# LED3.net
KiCad netlist of a schematic drawn in Altium Designer
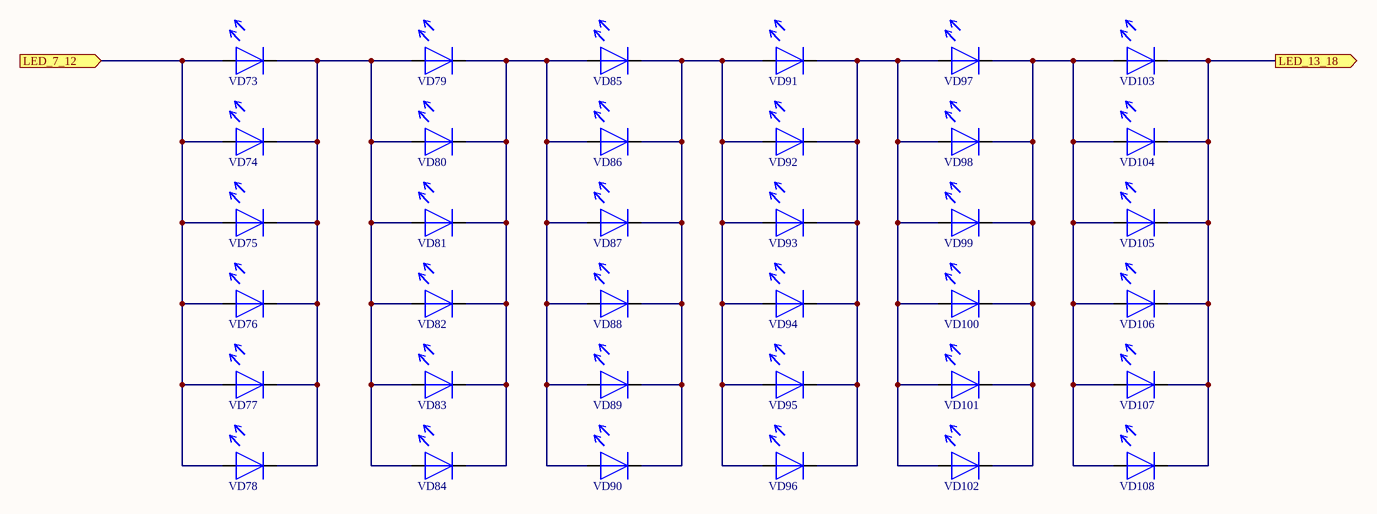
[diagram p0: LED3.SchDoc]

(export (version "E")
  (design (tool "Eeschema 10.0.6"))
  (components
    (comp (ref "VD73")
      (value "SPMWHT541MD5WAT0SB")
      (footprint "LED_Samsung")
      (libsource (lib "gprs_modem_2") (part "LED SPMWHT541MD5WAT0SB"))
    )
    (comp (ref "VD74")
      (value "SPMWHT541MD5WAT0SB")
      (footprint "LED_Samsung")
      (libsource (lib "gprs_modem_2") (part "LED SPMWHT541MD5WAT0SB"))
    )
    (comp (ref "VD75")
      (value "SPMWHT541MD5WAT0SB")
      (footprint "LED_Samsung")
      (libsource (lib "gprs_modem_2") (part "LED SPMWHT541MD5WAT0SB"))
    )
    (comp (ref "VD76")
      (value "SPMWHT541MD5WAT0SB")
      (footprint "LED_Samsung")
      (libsource (lib "gprs_modem_2") (part "LED SPMWHT541MD5WAT0SB"))
    )
    (comp (ref "VD77")
      (value "SPMWHT541MD5WAT0SB")
      (footprint "LED_Samsung")
      (libsource (lib "gprs_modem_2") (part "LED SPMWHT541MD5WAT0SB"))
    )
    (comp (ref "VD78")
      (value "SPMWHT541MD5WAT0SB")
      (footprint "LED_Samsung")
      (libsource (lib "gprs_modem_2") (part "LED SPMWHT541MD5WAT0SB"))
    )
    (comp (ref "VD79")
      (value "SPMWHT541MD5WAT0SB")
      (footprint "LED_Samsung")
      (libsource (lib "gprs_modem_2") (part "LED SPMWHT541MD5WAT0SB"))
    )
    (comp (ref "VD80")
      (value "SPMWHT541MD5WAT0SB")
      (footprint "LED_Samsung")
      (libsource (lib "gprs_modem_2") (part "LED SPMWHT541MD5WAT0SB"))
    )
    (comp (ref "VD81")
      (value "SPMWHT541MD5WAT0SB")
      (footprint "LED_Samsung")
      (libsource (lib "gprs_modem_2") (part "LED SPMWHT541MD5WAT0SB"))
    )
    (comp (ref "VD82")
      (value "SPMWHT541MD5WAT0SB")
      (footprint "LED_Samsung")
      (libsource (lib "gprs_modem_2") (part "LED SPMWHT541MD5WAT0SB"))
    )
    (comp (ref "VD83")
      (value "SPMWHT541MD5WAT0SB")
      (footprint "LED_Samsung")
      (libsource (lib "gprs_modem_2") (part "LED SPMWHT541MD5WAT0SB"))
    )
    (comp (ref "VD84")
      (value "SPMWHT541MD5WAT0SB")
      (footprint "LED_Samsung")
      (libsource (lib "gprs_modem_2") (part "LED SPMWHT541MD5WAT0SB"))
    )
    (comp (ref "VD85")
      (value "SPMWHT541MD5WAT0SB")
      (footprint "LED_Samsung")
      (libsource (lib "gprs_modem_2") (part "LED SPMWHT541MD5WAT0SB"))
    )
    (comp (ref "VD86")
      (value "SPMWHT541MD5WAT0SB")
      (footprint "LED_Samsung")
      (libsource (lib "gprs_modem_2") (part "LED SPMWHT541MD5WAT0SB"))
    )
    (comp (ref "VD87")
      (value "SPMWHT541MD5WAT0SB")
      (footprint "LED_Samsung")
      (libsource (lib "gprs_modem_2") (part "LED SPMWHT541MD5WAT0SB"))
    )
    (comp (ref "VD88")
      (value "SPMWHT541MD5WAT0SB")
      (footprint "LED_Samsung")
      (libsource (lib "gprs_modem_2") (part "LED SPMWHT541MD5WAT0SB"))
    )
    (comp (ref "VD89")
      (value "SPMWHT541MD5WAT0SB")
      (footprint "LED_Samsung")
      (libsource (lib "gprs_modem_2") (part "LED SPMWHT541MD5WAT0SB"))
    )
    (comp (ref "VD90")
      (value "SPMWHT541MD5WAT0SB")
      (footprint "LED_Samsung")
      (libsource (lib "gprs_modem_2") (part "LED SPMWHT541MD5WAT0SB"))
    )
    (comp (ref "VD91")
      (value "SPMWHT541MD5WAT0SB")
      (footprint "LED_Samsung")
      (libsource (lib "gprs_modem_2") (part "LED SPMWHT541MD5WAT0SB"))
    )
    (comp (ref "VD92")
      (value "SPMWHT541MD5WAT0SB")
      (footprint "LED_Samsung")
      (libsource (lib "gprs_modem_2") (part "LED SPMWHT541MD5WAT0SB"))
    )
    (comp (ref "VD93")
      (value "SPMWHT541MD5WAT0SB")
      (footprint "LED_Samsung")
      (libsource (lib "gprs_modem_2") (part "LED SPMWHT541MD5WAT0SB"))
    )
    (comp (ref "VD94")
      (value "SPMWHT541MD5WAT0SB")
      (footprint "LED_Samsung")
      (libsource (lib "gprs_modem_2") (part "LED SPMWHT541MD5WAT0SB"))
    )
    (comp (ref "VD95")
      (value "SPMWHT541MD5WAT0SB")
      (footprint "LED_Samsung")
      (libsource (lib "gprs_modem_2") (part "LED SPMWHT541MD5WAT0SB"))
    )
    (comp (ref "VD96")
      (value "SPMWHT541MD5WAT0SB")
      (footprint "LED_Samsung")
      (libsource (lib "gprs_modem_2") (part "LED SPMWHT541MD5WAT0SB"))
    )
    (comp (ref "VD97")
      (value "SPMWHT541MD5WAT0SB")
      (footprint "LED_Samsung")
      (libsource (lib "gprs_modem_2") (part "LED SPMWHT541MD5WAT0SB"))
    )
    (comp (ref "VD98")
      (value "SPMWHT541MD5WAT0SB")
      (footprint "LED_Samsung")
      (libsource (lib "gprs_modem_2") (part "LED SPMWHT541MD5WAT0SB"))
    )
    (comp (ref "VD99")
      (value "SPMWHT541MD5WAT0SB")
      (footprint "LED_Samsung")
      (libsource (lib "gprs_modem_2") (part "LED SPMWHT541MD5WAT0SB"))
    )
    (comp (ref "VD100")
      (value "SPMWHT541MD5WAT0SB")
      (footprint "LED_Samsung")
      (libsource (lib "gprs_modem_2") (part "LED SPMWHT541MD5WAT0SB"))
    )
    (comp (ref "VD101")
      (value "SPMWHT541MD5WAT0SB")
      (footprint "LED_Samsung")
      (libsource (lib "gprs_modem_2") (part "LED SPMWHT541MD5WAT0SB"))
    )
    (comp (ref "VD102")
      (value "SPMWHT541MD5WAT0SB")
      (footprint "LED_Samsung")
      (libsource (lib "gprs_modem_2") (part "LED SPMWHT541MD5WAT0SB"))
    )
    (comp (ref "VD103")
      (value "SPMWHT541MD5WAT0SB")
      (footprint "LED_Samsung")
      (libsource (lib "gprs_modem_2") (part "LED SPMWHT541MD5WAT0SB"))
    )
    (comp (ref "VD104")
      (value "SPMWHT541MD5WAT0SB")
      (footprint "LED_Samsung")
      (libsource (lib "gprs_modem_2") (part "LED SPMWHT541MD5WAT0SB"))
    )
    (comp (ref "VD105")
      (value "SPMWHT541MD5WAT0SB")
      (footprint "LED_Samsung")
      (libsource (lib "gprs_modem_2") (part "LED SPMWHT541MD5WAT0SB"))
    )
    (comp (ref "VD106")
      (value "SPMWHT541MD5WAT0SB")
      (footprint "LED_Samsung")
      (libsource (lib "gprs_modem_2") (part "LED SPMWHT541MD5WAT0SB"))
    )
    (comp (ref "VD107")
      (value "SPMWHT541MD5WAT0SB")
      (footprint "LED_Samsung")
      (libsource (lib "gprs_modem_2") (part "LED SPMWHT541MD5WAT0SB"))
    )
    (comp (ref "VD108")
      (value "SPMWHT541MD5WAT0SB")
      (footprint "LED_Samsung")
      (libsource (lib "gprs_modem_2") (part "LED SPMWHT541MD5WAT0SB"))
    )
  )
  (nets
    (net (code "1") (name "/LED_7_12") (class "Default")
      (node (ref "VD73") (pin "1") (pintype "passive"))
      (node (ref "VD74") (pin "1") (pintype "passive"))
      (node (ref "VD75") (pin "1") (pintype "passive"))
      (node (ref "VD76") (pin "1") (pintype "passive"))
      (node (ref "VD77") (pin "1") (pintype "passive"))
      (node (ref "VD78") (pin "1") (pintype "passive"))
    )
    (net (code "2") (name "/LED_13_18") (class "Default")
      (node (ref "VD103") (pin "2") (pintype "passive"))
      (node (ref "VD104") (pin "2") (pintype "passive"))
      (node (ref "VD105") (pin "2") (pintype "passive"))
      (node (ref "VD106") (pin "2") (pintype "passive"))
      (node (ref "VD107") (pin "2") (pintype "passive"))
      (node (ref "VD108") (pin "2") (pintype "passive"))
    )
    (net (code "3") (name "Net-(VD73-Pad2)") (class "Default")
      (node (ref "VD73") (pin "2") (pintype "passive"))
      (node (ref "VD74") (pin "2") (pintype "passive"))
      (node (ref "VD75") (pin "2") (pintype "passive"))
      (node (ref "VD76") (pin "2") (pintype "passive"))
      (node (ref "VD77") (pin "2") (pintype "passive"))
      (node (ref "VD78") (pin "2") (pintype "passive"))
      (node (ref "VD79") (pin "1") (pintype "passive"))
      (node (ref "VD80") (pin "1") (pintype "passive"))
      (node (ref "VD81") (pin "1") (pintype "passive"))
      (node (ref "VD82") (pin "1") (pintype "passive"))
      (node (ref "VD83") (pin "1") (pintype "passive"))
      (node (ref "VD84") (pin "1") (pintype "passive"))
    )
    (net (code "4") (name "Net-(VD79-Pad2)") (class "Default")
      (node (ref "VD79") (pin "2") (pintype "passive"))
      (node (ref "VD80") (pin "2") (pintype "passive"))
      (node (ref "VD81") (pin "2") (pintype "passive"))
      (node (ref "VD82") (pin "2") (pintype "passive"))
      (node (ref "VD83") (pin "2") (pintype "passive"))
      (node (ref "VD84") (pin "2") (pintype "passive"))
      (node (ref "VD85") (pin "1") (pintype "passive"))
      (node (ref "VD86") (pin "1") (pintype "passive"))
      (node (ref "VD87") (pin "1") (pintype "passive"))
      (node (ref "VD88") (pin "1") (pintype "passive"))
      (node (ref "VD89") (pin "1") (pintype "passive"))
      (node (ref "VD90") (pin "1") (pintype "passive"))
    )
    (net (code "5") (name "Net-(VD85-Pad2)") (class "Default")
      (node (ref "VD85") (pin "2") (pintype "passive"))
      (node (ref "VD86") (pin "2") (pintype "passive"))
      (node (ref "VD87") (pin "2") (pintype "passive"))
      (node (ref "VD88") (pin "2") (pintype "passive"))
      (node (ref "VD89") (pin "2") (pintype "passive"))
      (node (ref "VD90") (pin "2") (pintype "passive"))
      (node (ref "VD91") (pin "1") (pintype "passive"))
      (node (ref "VD92") (pin "1") (pintype "passive"))
      (node (ref "VD93") (pin "1") (pintype "passive"))
      (node (ref "VD94") (pin "1") (pintype "passive"))
      (node (ref "VD95") (pin "1") (pintype "passive"))
      (node (ref "VD96") (pin "1") (pintype "passive"))
    )
    (net (code "6") (name "Net-(VD100-Pad1)") (class "Default")
      (node (ref "VD100") (pin "1") (pintype "passive"))
      (node (ref "VD101") (pin "1") (pintype "passive"))
      (node (ref "VD102") (pin "1") (pintype "passive"))
      (node (ref "VD91") (pin "2") (pintype "passive"))
      (node (ref "VD92") (pin "2") (pintype "passive"))
      (node (ref "VD93") (pin "2") (pintype "passive"))
      (node (ref "VD94") (pin "2") (pintype "passive"))
      (node (ref "VD95") (pin "2") (pintype "passive"))
      (node (ref "VD96") (pin "2") (pintype "passive"))
      (node (ref "VD97") (pin "1") (pintype "passive"))
      (node (ref "VD98") (pin "1") (pintype "passive"))
      (node (ref "VD99") (pin "1") (pintype "passive"))
    )
    (net (code "7") (name "Net-(VD100-Pad2)") (class "Default")
      (node (ref "VD100") (pin "2") (pintype "passive"))
      (node (ref "VD101") (pin "2") (pintype "passive"))
      (node (ref "VD102") (pin "2") (pintype "passive"))
      (node (ref "VD103") (pin "1") (pintype "passive"))
      (node (ref "VD104") (pin "1") (pintype "passive"))
      (node (ref "VD105") (pin "1") (pintype "passive"))
      (node (ref "VD106") (pin "1") (pintype "passive"))
      (node (ref "VD107") (pin "1") (pintype "passive"))
      (node (ref "VD108") (pin "1") (pintype "passive"))
      (node (ref "VD97") (pin "2") (pintype "passive"))
      (node (ref "VD98") (pin "2") (pintype "passive"))
      (node (ref "VD99") (pin "2") (pintype "passive"))
    )
  )
)
